# tsal-logic.net
KiCad netlist of a schematic drawn in Altium Designer
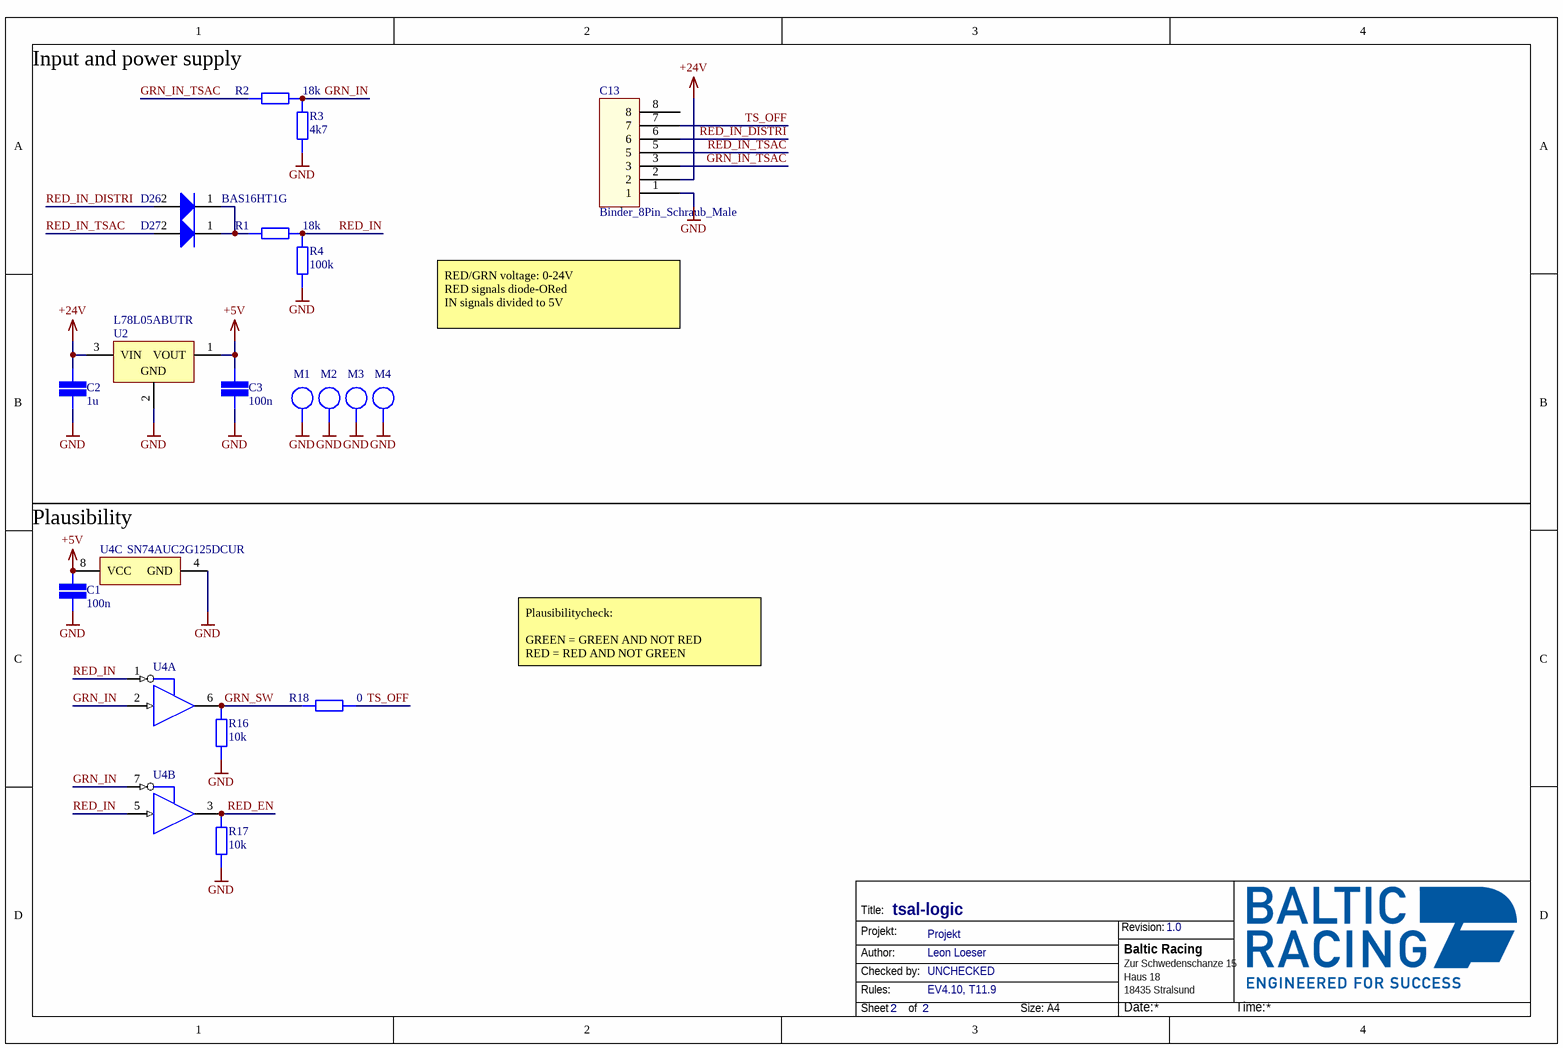
[diagram p0: tsal-logic.SchDoc]

(export (version "E")
  (design (tool "Eeschema 10.0.6"))
  (components
    (comp (ref "C1")
      (value "100n")
      (footprint "CAP 0603/1608")
      (description "Capacitor with multiple Footprints")
      (fields (field (name "Comment") "SMD Capacitor"))
      (libsource (lib "Standardbauteile") (part "SMD Capacitor"))
    )
    (comp (ref "C2")
      (value "1u")
      (footprint "CAP 0805/2012")
      (description "Capacitor with multiple Footprints")
      (fields (field (name "Comment") "SMD Capacitor"))
      (libsource (lib "Standardbauteile") (part "SMD Capacitor"))
    )
    (comp (ref "C3")
      (value "100n")
      (footprint "CAP 0603/1608")
      (description "Capacitor with multiple Footprints")
      (fields (field (name "Comment") "SMD Capacitor"))
      (libsource (lib "Standardbauteile") (part "SMD Capacitor"))
    )
    (comp (ref "C13")
      (value "Binder_8Pin_Schraub_Male")
      (footprint "09 0427 30 08")
      (libsource (lib "Eric") (part "Binder_8Pin_Schraub_Male"))
    )
    (comp (ref "D26")
      (value "BAS16HT1G")
      (footprint "ONSC-SOD-323-2-477-02_V")
      (description "Switching Diode, 2-Pin SOD-323, Pb-Free, Tape and Reel")
      (fields (field (name "MANUFACTURER") "On Semiconductor"))
      (libsource (lib "Altium Content Vault") (part "ONSC-D-K1A2-2"))
    )
    (comp (ref "D27")
      (value "BAS16HT1G")
      (footprint "ONSC-SOD-323-2-477-02_V")
      (description "Switching Diode, 2-Pin SOD-323, Pb-Free, Tape and Reel")
      (fields (field (name "MANUFACTURER") "On Semiconductor"))
      (libsource (lib "Altium Content Vault") (part "ONSC-D-K1A2-2"))
    )
    (comp (ref "M1")
      (value "mounting pad")
      (footprint "MOUNTING_PAD_M3")
      (libsource (lib "Standardbauteile") (part "mounting pad"))
    )
    (comp (ref "M2")
      (value "mounting pad")
      (footprint "MOUNTING_PAD_M3")
      (libsource (lib "Standardbauteile") (part "mounting pad"))
    )
    (comp (ref "M3")
      (value "mounting pad")
      (footprint "MOUNTING_PAD_M3")
      (libsource (lib "Standardbauteile") (part "mounting pad"))
    )
    (comp (ref "M4")
      (value "mounting pad")
      (footprint "MOUNTING_PAD_M3")
      (libsource (lib "Standardbauteile") (part "mounting pad"))
    )
    (comp (ref "R1")
      (value "18k")
      (footprint "STACKPOLE CSR0603")
      (description "Resistor with multiple footprints")
      (fields (field (name "Comment") "SMD Resistor"))
      (libsource (lib "Standardbauteile") (part "SMD Resistor"))
    )
    (comp (ref "R2")
      (value "18k")
      (footprint "STACKPOLE CSR0603")
      (description "Resistor with multiple footprints")
      (fields (field (name "Comment") "SMD Resistor"))
      (libsource (lib "Standardbauteile") (part "SMD Resistor"))
    )
    (comp (ref "R3")
      (value "4k7")
      (footprint "STACKPOLE CSR0603")
      (description "Resistor with multiple footprints")
      (fields (field (name "Comment") "SMD Resistor"))
      (libsource (lib "Standardbauteile") (part "SMD Resistor"))
    )
    (comp (ref "R4")
      (value "100k")
      (footprint "STACKPOLE CSR0603")
      (description "Resistor with multiple footprints")
      (fields (field (name "Comment") "SMD Resistor"))
      (libsource (lib "Standardbauteile") (part "SMD Resistor"))
    )
    (comp (ref "R16")
      (value "10k")
      (footprint "STACKPOLE CSR0603")
      (description "Resistor with multiple footprints")
      (fields (field (name "Comment") "SMD Resistor"))
      (libsource (lib "Standardbauteile") (part "SMD Resistor"))
    )
    (comp (ref "R17")
      (value "10k")
      (footprint "STACKPOLE CSR0603")
      (description "Resistor with multiple footprints")
      (fields (field (name "Comment") "SMD Resistor"))
      (libsource (lib "Standardbauteile") (part "SMD Resistor"))
    )
    (comp (ref "R18")
      (value "0")
      (footprint "STACKPOLE CSR0603")
      (description "Resistor with multiple footprints")
      (fields (field (name "Comment") "SMD Resistor"))
      (libsource (lib "Standardbauteile") (part "SMD Resistor"))
    )
    (comp (ref "U2")
      (value "L78L05ABUTR")
      (footprint "SOT-89_N")
      (description "Positive Voltage Regulator, 5V, 4-Pin SOT-89, Tape and Reel")
      (libsource (lib "Altium Content Vault") (part "PM-REG-7805-SIL3"))
    )
    (comp (ref "U4")
      (value "SN74AUC2G125DCUR")
      (footprint "DCU0008A_M")
      (description "Dual Bus Buffer Gate with 3-State Outputs, DCU0008A, LARGE T&R")
      (fields
        (field (name "MANUFACTURER") "Texas Instruments")
        (field (name "GENERIC PART NUMBER") "SN74AUC2G125")
      )
      (libsource (lib "Altium Content Vault") (part "TI-SN74XXX2G125-XX-8"))
    )
  )
  (nets
    (net (code "1") (name "+5V") (class "Default")
      (node (ref "C1") (pin "2") (pinfunction "2_2") (pintype "passive"))
      (node (ref "C3") (pin "2") (pinfunction "2_2") (pintype "passive"))
      (node (ref "U2") (pin "1") (pinfunction "VOUT_1") (pintype "power_in"))
      (node (ref "U4") (pin "8") (pinfunction "VCC_8") (pintype "power_in"))
    )
    (net (code "2") (name "+24V") (class "Default")
      (node (ref "C13") (pin "2") (pinfunction "2_2") (pintype "passive"))
      (node (ref "C2") (pin "2") (pinfunction "2_2") (pintype "passive"))
      (node (ref "U2") (pin "3") (pinfunction "VIN_3") (pintype "power_in"))
    )
    (net (code "3") (name "/GRN_IN") (class "Default")
      (node (ref "R2") (pin "2") (pinfunction "2_2") (pintype "passive"))
      (node (ref "R3") (pin "2") (pinfunction "2_2") (pintype "passive"))
      (node (ref "U4") (pin "2") (pinfunction "1A_2") (pintype "input"))
      (node (ref "U4") (pin "7") (pinfunction "2~{OE}_7") (pintype "input"))
    )
    (net (code "4") (name "/GRN_IN_TSAC") (class "Default")
      (node (ref "C13") (pin "3") (pinfunction "3_3") (pintype "passive"))
      (node (ref "R2") (pin "1") (pinfunction "1_1") (pintype "passive"))
    )
    (net (code "5") (name "/GRN_SW") (class "Default")
      (node (ref "R16") (pin "2") (pinfunction "2_2") (pintype "passive"))
      (node (ref "R18") (pin "1") (pinfunction "1_1") (pintype "passive"))
      (node (ref "U4") (pin "6") (pinfunction "1Y_6") (pintype "tri_state"))
    )
    (net (code "6") (name "/RED_EN") (class "Default")
      (node (ref "R17") (pin "2") (pinfunction "2_2") (pintype "passive"))
      (node (ref "U4") (pin "3") (pinfunction "2Y_3") (pintype "tri_state"))
    )
    (net (code "7") (name "/RED_IN") (class "Default")
      (node (ref "R1") (pin "2") (pinfunction "2_2") (pintype "passive"))
      (node (ref "R4") (pin "2") (pinfunction "2_2") (pintype "passive"))
      (node (ref "U4") (pin "1") (pinfunction "1~{OE}_1") (pintype "input"))
      (node (ref "U4") (pin "5") (pinfunction "2A_5") (pintype "input"))
    )
    (net (code "8") (name "/RED_IN_DISTRI") (class "Default")
      (node (ref "C13") (pin "6") (pinfunction "6_6") (pintype "passive"))
      (node (ref "D26") (pin "2") (pinfunction "A_2") (pintype "passive"))
    )
    (net (code "9") (name "/RED_IN_TSAC") (class "Default")
      (node (ref "C13") (pin "5") (pinfunction "5_5") (pintype "passive"))
      (node (ref "D27") (pin "2") (pinfunction "A_2") (pintype "passive"))
    )
    (net (code "10") (name "/TS_OFF") (class "Default")
      (node (ref "C13") (pin "7") (pinfunction "7_7") (pintype "passive"))
      (node (ref "R18") (pin "2") (pinfunction "2_2") (pintype "passive"))
    )
    (net (code "11") (name "GND") (class "Default")
      (node (ref "C1") (pin "1") (pinfunction "1_1") (pintype "passive"))
      (node (ref "C13") (pin "1") (pinfunction "1_1") (pintype "passive"))
      (node (ref "C2") (pin "1") (pinfunction "1_1") (pintype "passive"))
      (node (ref "C3") (pin "1") (pinfunction "1_1") (pintype "passive"))
      (node (ref "M1") (pin "1") (pintype "passive"))
      (node (ref "M2") (pin "1") (pintype "passive"))
      (node (ref "M3") (pin "1") (pintype "passive"))
      (node (ref "M4") (pin "1") (pintype "passive"))
      (node (ref "R16") (pin "1") (pinfunction "1_1") (pintype "passive"))
      (node (ref "R17") (pin "1") (pinfunction "1_1") (pintype "passive"))
      (node (ref "R3") (pin "1") (pinfunction "1_1") (pintype "passive"))
      (node (ref "R4") (pin "1") (pinfunction "1_1") (pintype "passive"))
      (node (ref "U2") (pin "2") (pinfunction "GND_2") (pintype "power_in"))
      (node (ref "U4") (pin "4") (pinfunction "GND_4") (pintype "power_in"))
    )
    (net (code "12") (name "Net-(D26-K)") (class "Default")
      (node (ref "D26") (pin "1") (pinfunction "K_1") (pintype "passive"))
      (node (ref "D27") (pin "1") (pinfunction "K_1") (pintype "passive"))
      (node (ref "R1") (pin "1") (pinfunction "1_1") (pintype "passive"))
    )
    (net (code "13") (name "unconnected-(C13-Pad8)") (class "Default")
      (node (ref "C13") (pin "8") (pinfunction "8_8") (pintype "passive"))
    )
  )
)
